# RTU_LMG_DO.net
KiCad netlist of a schematic drawn in Altium Designer
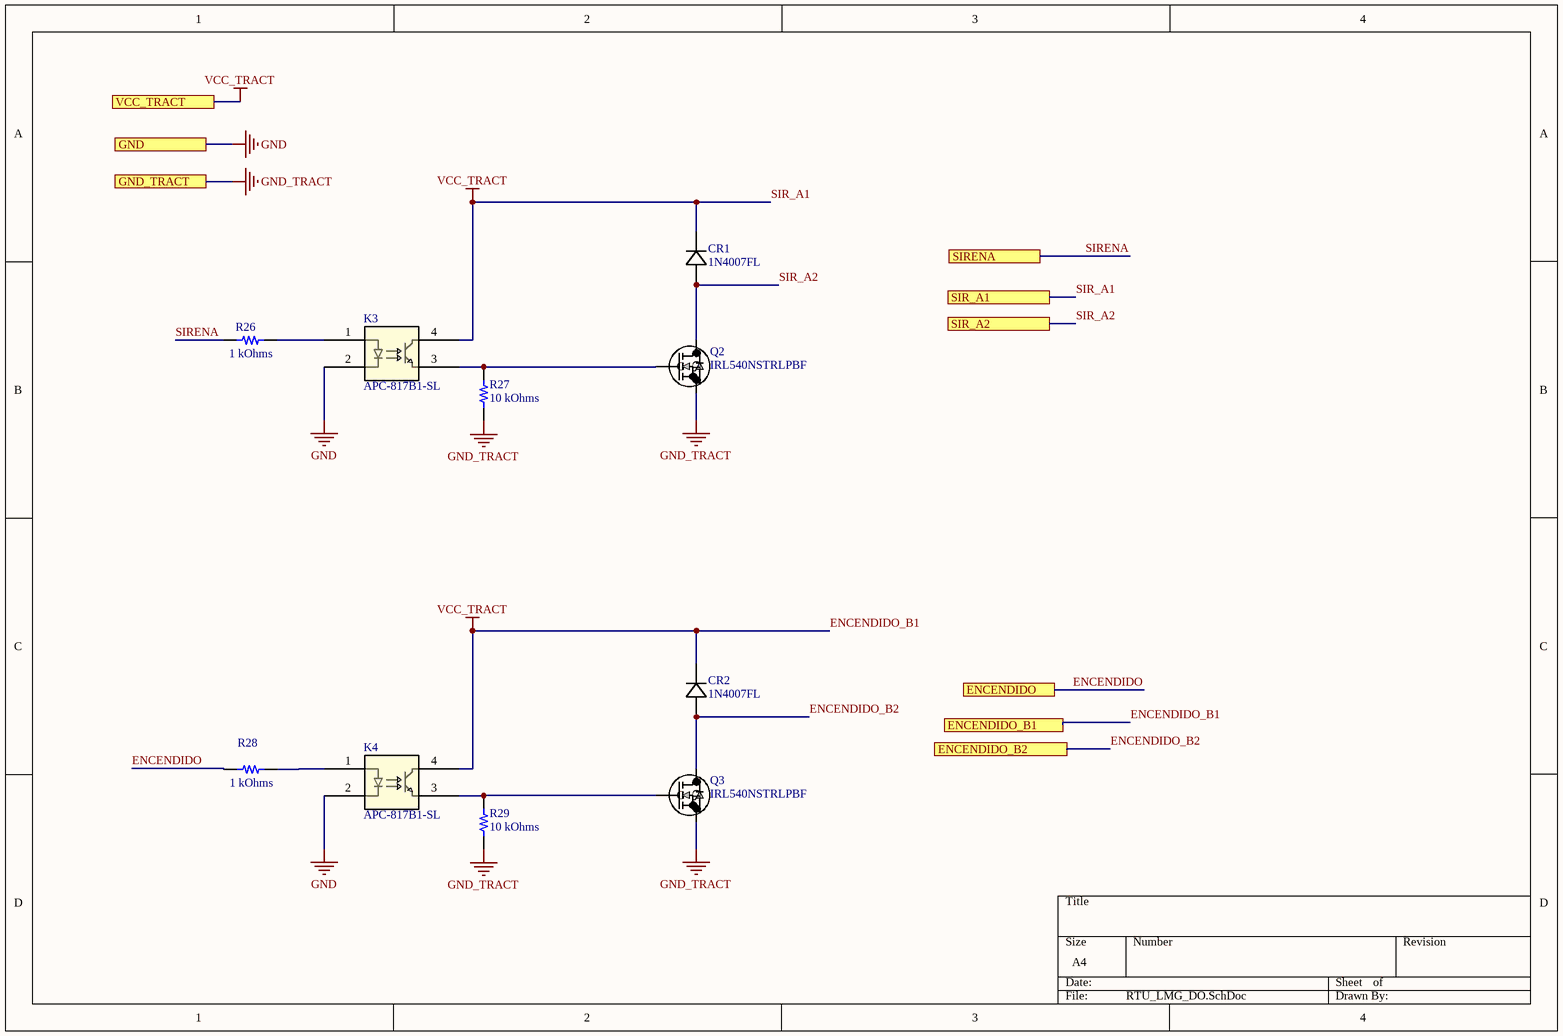
[diagram p0: RTU_LMG_DO.SchDoc]

(export (version "E")
  (design (tool "Eeschema 10.0.6"))
  (components
    (comp (ref "CR1")
      (value "1N4007FL")
      (footprint "CR_SOD-123FL_SME")
      (description "Description")
      (fields (field (name "COPYRIGHT") "Copyright (C) 2025 Ultra Librarian. All rights reserved."))
      (libsource (lib "1N4007FL") (part "1N4007FL"))
    )
    (comp (ref "CR2")
      (value "1N4007FL")
      (footprint "CR_SOD-123FL_SME")
      (description "Description")
      (fields (field (name "COPYRIGHT") "Copyright (C) 2025 Ultra Librarian. All rights reserved."))
      (libsource (lib "1N4007FL") (part "1N4007FL"))
    )
    (comp (ref "K3")
      (value "APC-817B1-SL")
      (footprint "APC-817xx-SL_AMB")
      (description "Description")
      (fields (field (name "COPYRIGHT") "Copyright (C) 2025 Ultra Librarian. All rights reserved."))
      (libsource (lib "APC-817B1-SL") (part "APC-817B1-SL"))
    )
    (comp (ref "K4")
      (value "APC-817B1-SL")
      (footprint "APC-817xx-SL_AMB")
      (description "Description")
      (fields (field (name "COPYRIGHT") "Copyright (C) 2025 Ultra Librarian. All rights reserved."))
      (libsource (lib "APC-817B1-SL") (part "APC-817B1-SL"))
    )
    (comp (ref "Q2")
      (value "IRL540NSTRLPBF")
      (footprint "NMOSGSD_D2PAK_IRL540NSTRLPBF_INF")
      (description "Description")
      (fields (field (name "COPYRIGHT") "Copyright (C) 2025 Ultra Librarian. All rights reserved."))
      (libsource (lib "IRL540NSTRLPBF") (part "IRL540NSTRLPBF"))
    )
    (comp (ref "Q3")
      (value "IRL540NSTRLPBF")
      (footprint "NMOSGSD_D2PAK_IRL540NSTRLPBF_INF")
      (description "Description")
      (fields (field (name "COPYRIGHT") "Copyright (C) 2025 Ultra Librarian. All rights reserved."))
      (libsource (lib "IRL540NSTRLPBF") (part "IRL540NSTRLPBF"))
    )
    (comp (ref "R26")
      (value "1 kOhms")
      (footprint "RES 0402_1005")
      (description "RES SMD 1K OHM 0.1% 1/16W 0402")
      (fields (field (name "PART NUMBER") "AT0402BRD071KL") (field (name "MANUFACTURER") "Yageo"))
      (libsource (lib "Celestial Altium Library - altium_library") (part "Resistor"))
    )
    (comp (ref "R27")
      (value "10 kOhms")
      (footprint "RES 0603_1608")
      (description "RES 10K OHM 1% 1/10W 0603")
      (fields (field (name "PART NUMBER") "RC0603FR-0710KL") (field (name "MANUFACTURER") "Yageo"))
      (libsource (lib "Celestial Altium Library - altium_library") (part "Resistor"))
    )
    (comp (ref "R28")
      (value "1 kOhms")
      (footprint "RES 0402_1005")
      (description "RES SMD 1K OHM 0.1% 1/16W 0402")
      (fields (field (name "PART NUMBER") "AT0402BRD071KL") (field (name "MANUFACTURER") "Yageo"))
      (libsource (lib "Celestial Altium Library - altium_library") (part "Resistor"))
    )
    (comp (ref "R29")
      (value "10 kOhms")
      (footprint "RES 0603_1608")
      (description "RES 10K OHM 1% 1/10W 0603")
      (fields (field (name "PART NUMBER") "RC0603FR-0710KL") (field (name "MANUFACTURER") "Yageo"))
      (libsource (lib "Celestial Altium Library - altium_library") (part "Resistor"))
    )
  )
  (nets
    (net (code "1") (name "/ENCENDIDO") (class "Default")
      (node (ref "R28") (pin "1") (pinfunction "1_1") (pintype "passive"))
    )
    (net (code "2") (name "/ENCENDIDO_B2") (class "Default")
      (node (ref "CR2") (pin "2") (pinfunction "ANODE_2") (pintype "passive"))
      (node (ref "Q3") (pin "3") (pinfunction "D_3") (pintype "passive"))
    )
    (net (code "3") (name "/SIRENA") (class "Default")
      (node (ref "R26") (pin "1") (pinfunction "1_1") (pintype "passive"))
    )
    (net (code "4") (name "/SIR_A2") (class "Default")
      (node (ref "CR1") (pin "2") (pinfunction "ANODE_2") (pintype "passive"))
      (node (ref "Q2") (pin "3") (pinfunction "D_3") (pintype "passive"))
    )
    (net (code "5") (name "GND") (class "Default")
      (node (ref "K3") (pin "2") (pinfunction "2_2") (pintype "passive"))
      (node (ref "K4") (pin "2") (pinfunction "2_2") (pintype "passive"))
    )
    (net (code "6") (name "GND_TRACT") (class "Default")
      (node (ref "Q2") (pin "2") (pinfunction "S_2") (pintype "passive"))
      (node (ref "Q3") (pin "2") (pinfunction "S_2") (pintype "passive"))
      (node (ref "R27") (pin "1") (pinfunction "1_1") (pintype "passive"))
      (node (ref "R29") (pin "1") (pinfunction "1_1") (pintype "passive"))
    )
    (net (code "7") (name "Net-(K3-Pad1)") (class "Default")
      (node (ref "K3") (pin "1") (pinfunction "1_1") (pintype "passive"))
      (node (ref "R26") (pin "2") (pinfunction "2_2") (pintype "passive"))
    )
    (net (code "8") (name "Net-(K4-Pad1)") (class "Default")
      (node (ref "K4") (pin "1") (pinfunction "1_1") (pintype "passive"))
      (node (ref "R28") (pin "2") (pinfunction "2_2") (pintype "passive"))
    )
    (net (code "9") (name "Net-(Q2-G)") (class "Default")
      (node (ref "K3") (pin "3") (pinfunction "3_3") (pintype "passive"))
      (node (ref "Q2") (pin "1") (pinfunction "G_1") (pintype "passive"))
      (node (ref "R27") (pin "2") (pinfunction "2_2") (pintype "passive"))
    )
    (net (code "10") (name "Net-(Q3-G)") (class "Default")
      (node (ref "K4") (pin "3") (pinfunction "3_3") (pintype "passive"))
      (node (ref "Q3") (pin "1") (pinfunction "G_1") (pintype "passive"))
      (node (ref "R29") (pin "2") (pinfunction "2_2") (pintype "passive"))
    )
    (net (code "11") (name "VCC_TRACT") (class "Default")
      (node (ref "CR1") (pin "1") (pinfunction "CATHODE_1") (pintype "passive"))
      (node (ref "CR2") (pin "1") (pinfunction "CATHODE_1") (pintype "passive"))
      (node (ref "K3") (pin "4") (pinfunction "4_4") (pintype "passive"))
      (node (ref "K4") (pin "4") (pinfunction "4_4") (pintype "passive"))
    )
  )
)
